# 03_MCU.net
KiCad netlist of a schematic drawn in Altium Designer
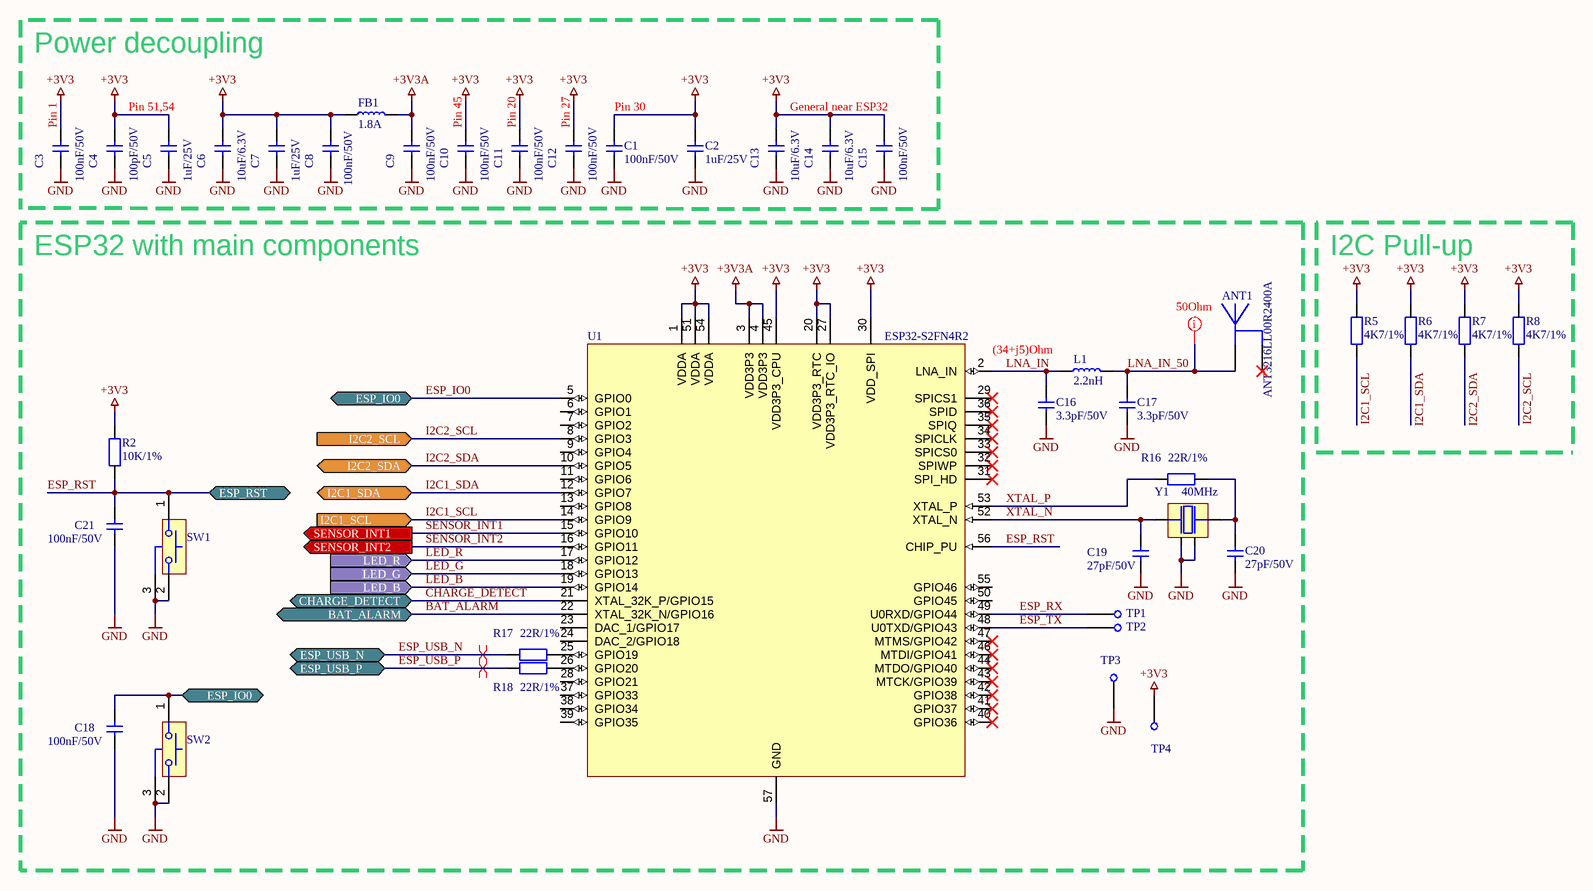
[diagram p0: 03 MCU.SchDoc]

(export (version "E")
  (design (tool "Eeschema 10.0.6"))
  (components
    (comp (ref "ANT1")
      (value "ANT3216LL00R2400A")
      (footprint "INDC3216X14N")
      (description "1206  Antennas ROHS")
      (fields (field (name "MANUFACTURER") "YAGEO"))
      (libsource (lib "altium_symbol") (part "ANT3216LL00R2400A"))
    )
    (comp (ref "C1")
      (value "100nF/50V")
      (footprint "CAPC1005X06N")
      (description "16V 100nF X7R ±10% 0402  Multilayer Ceramic Capacitors MLCC - SMD/SMT ROHS")
      (fields
        (field (name "MANUFACTURER") "Samsung Electro-Mechanics")
        (field (name "MFR_PART_NUMBER") "CL05B104KO5NNNC")
      )
      (libsource (lib "altium_symbol") (part "CL05B104KO5NNNC"))
    )
    (comp (ref "C2")
      (value "1uF/25V")
      (footprint "CAPC1005X06N")
      (description "25V 1uF X5R ±10% 0402  Multilayer Ceramic Capacitors MLCC - SMD/SMT ROHS")
      (fields
        (field (name "MANUFACTURER") "Samsung Electro-Mechanics")
        (field (name "MFR_PART_NUMBER") "CL05A105KA5NQNC")
      )
      (libsource (lib "altium_symbol") (part "CL05A105KA5NQNC"))
    )
    (comp (ref "C3")
      (value "100nF/50V")
      (footprint "CAPC1005X06N")
      (description "16V 100nF X7R ±10% 0402  Multilayer Ceramic Capacitors MLCC - SMD/SMT ROHS")
      (fields
        (field (name "MANUFACTURER") "Samsung Electro-Mechanics")
        (field (name "MFR_PART_NUMBER") "CL05B104KO5NNNC")
      )
      (libsource (lib "altium_symbol") (part "CL05B104KO5NNNC"))
    )
    (comp (ref "C4")
      (value "100pF/50V")
      (footprint "CAPC1005X06N")
      (description "50V 100pF C0G ±5% 0402  Multilayer Ceramic Capacitors MLCC - SMD/SMT ROHS")
      (fields
        (field (name "MANUFACTURER") "FH (Guangdong Fenghua Advanced Tech)")
        (field (name "MFR_PART_NUMBER") "0402CG101J500NT")
      )
      (libsource (lib "altium_symbol") (part "0402CG101J500NT"))
    )
    (comp (ref "C5")
      (value "1uF/25V")
      (footprint "CAPC1005X06N")
      (description "25V 1uF X5R ±10% 0402  Multilayer Ceramic Capacitors MLCC - SMD/SMT ROHS")
      (fields
        (field (name "MANUFACTURER") "Samsung Electro-Mechanics")
        (field (name "MFR_PART_NUMBER") "CL05A105KA5NQNC")
      )
      (libsource (lib "altium_symbol") (part "CL05A105KA5NQNC"))
    )
    (comp (ref "C6")
      (value "10uF/6.3V")
      (footprint "CAPC1005X06N")
      (description "6.3V 10uF X5R ±20% 0402  Multilayer Ceramic Capacitors MLCC - SMD/SMT ROHS")
      (fields
        (field (name "MANUFACTURER") "Samsung Electro-Mechanics")
        (field (name "MFR_PART_NUMBER") "CL05A106MQ5NUNC")
      )
      (libsource (lib "altium_symbol") (part "CL05A106MQ5NUNC"))
    )
    (comp (ref "C7")
      (value "1uF/25V")
      (footprint "CAPC1005X06N")
      (description "25V 1uF X5R ±10% 0402  Multilayer Ceramic Capacitors MLCC - SMD/SMT ROHS")
      (fields
        (field (name "MANUFACTURER") "Samsung Electro-Mechanics")
        (field (name "MFR_PART_NUMBER") "CL05A105KA5NQNC")
      )
      (libsource (lib "altium_symbol") (part "CL05A105KA5NQNC"))
    )
    (comp (ref "C8")
      (value "100nF/50V")
      (footprint "CAPC1005X06N")
      (description "16V 100nF X7R ±10% 0402  Multilayer Ceramic Capacitors MLCC - SMD/SMT ROHS")
      (fields
        (field (name "MANUFACTURER") "Samsung Electro-Mechanics")
        (field (name "MFR_PART_NUMBER") "CL05B104KO5NNNC")
      )
      (libsource (lib "altium_symbol") (part "CL05B104KO5NNNC"))
    )
    (comp (ref "C9")
      (value "100nF/50V")
      (footprint "CAPC1005X06N")
      (description "16V 100nF X7R ±10% 0402  Multilayer Ceramic Capacitors MLCC - SMD/SMT ROHS")
      (fields
        (field (name "MANUFACTURER") "Samsung Electro-Mechanics")
        (field (name "MFR_PART_NUMBER") "CL05B104KO5NNNC")
      )
      (libsource (lib "altium_symbol") (part "CL05B104KO5NNNC"))
    )
    (comp (ref "C10")
      (value "100nF/50V")
      (footprint "CAPC1005X06N")
      (description "16V 100nF X7R ±10% 0402  Multilayer Ceramic Capacitors MLCC - SMD/SMT ROHS")
      (fields
        (field (name "MANUFACTURER") "Samsung Electro-Mechanics")
        (field (name "MFR_PART_NUMBER") "CL05B104KO5NNNC")
      )
      (libsource (lib "altium_symbol") (part "CL05B104KO5NNNC"))
    )
    (comp (ref "C11")
      (value "100nF/50V")
      (footprint "CAPC1005X06N")
      (description "16V 100nF X7R ±10% 0402  Multilayer Ceramic Capacitors MLCC - SMD/SMT ROHS")
      (fields
        (field (name "MANUFACTURER") "Samsung Electro-Mechanics")
        (field (name "MFR_PART_NUMBER") "CL05B104KO5NNNC")
      )
      (libsource (lib "altium_symbol") (part "CL05B104KO5NNNC"))
    )
    (comp (ref "C12")
      (value "100nF/50V")
      (footprint "CAPC1005X06N")
      (description "16V 100nF X7R ±10% 0402  Multilayer Ceramic Capacitors MLCC - SMD/SMT ROHS")
      (fields
        (field (name "MANUFACTURER") "Samsung Electro-Mechanics")
        (field (name "MFR_PART_NUMBER") "CL05B104KO5NNNC")
      )
      (libsource (lib "altium_symbol") (part "CL05B104KO5NNNC"))
    )
    (comp (ref "C13")
      (value "10uF/6.3V")
      (footprint "CAPC1005X06N")
      (description "6.3V 10uF X5R ±20% 0402  Multilayer Ceramic Capacitors MLCC - SMD/SMT ROHS")
      (fields
        (field (name "MANUFACTURER") "Samsung Electro-Mechanics")
        (field (name "MFR_PART_NUMBER") "CL05A106MQ5NUNC")
      )
      (libsource (lib "altium_symbol") (part "CL05A106MQ5NUNC"))
    )
    (comp (ref "C14")
      (value "10uF/6.3V")
      (footprint "CAPC1005X06N")
      (description "6.3V 10uF X5R ±20% 0402  Multilayer Ceramic Capacitors MLCC - SMD/SMT ROHS")
      (fields
        (field (name "MANUFACTURER") "Samsung Electro-Mechanics")
        (field (name "MFR_PART_NUMBER") "CL05A106MQ5NUNC")
      )
      (libsource (lib "altium_symbol") (part "CL05A106MQ5NUNC"))
    )
    (comp (ref "C15")
      (value "100nF/50V")
      (footprint "CAPC1005X06N")
      (description "16V 100nF X7R ±10% 0402  Multilayer Ceramic Capacitors MLCC - SMD/SMT ROHS")
      (fields
        (field (name "MANUFACTURER") "Samsung Electro-Mechanics")
        (field (name "MFR_PART_NUMBER") "CL05B104KO5NNNC")
      )
      (libsource (lib "altium_symbol") (part "CL05B104KO5NNNC"))
    )
    (comp (ref "C16")
      (value "3.3pF/50V")
      (footprint "CAPC1005X06N")
      (description "50V 3.3pF C0G ±0.25pF 0402  Multilayer Ceramic Capacitors MLCC - SMD/SMT ROHS")
      (fields
        (field (name "MANUFACTURER") "FH (Guangdong Fenghua Advanced Tech)")
        (field (name "MFR_PART_NUMBER") "0402CG3R3C500NT")
      )
      (libsource (lib "altium_symbol") (part "0402CG3R3C500NT"))
    )
    (comp (ref "C17")
      (value "3.3pF/50V")
      (footprint "CAPC1005X06N")
      (description "50V 3.3pF C0G ±0.25pF 0402  Multilayer Ceramic Capacitors MLCC - SMD/SMT ROHS")
      (fields
        (field (name "MANUFACTURER") "FH (Guangdong Fenghua Advanced Tech)")
        (field (name "MFR_PART_NUMBER") "0402CG3R3C500NT")
      )
      (libsource (lib "altium_symbol") (part "0402CG3R3C500NT"))
    )
    (comp (ref "C18")
      (value "100nF/50V")
      (footprint "CAPC1005X06N")
      (description "16V 100nF X7R ±10% 0402  Multilayer Ceramic Capacitors MLCC - SMD/SMT ROHS")
      (fields
        (field (name "MANUFACTURER") "Samsung Electro-Mechanics")
        (field (name "MFR_PART_NUMBER") "CL05B104KO5NNNC")
      )
      (libsource (lib "altium_symbol") (part "CL05B104KO5NNNC"))
    )
    (comp (ref "C19")
      (value "27pF/50V")
      (footprint "CAPC1005X06N")
      (description "50V 27pF C0G ±5% 0402  Multilayer Ceramic Capacitors MLCC - SMD/SMT ROHS")
      (fields
        (field (name "MANUFACTURER") "FH (Guangdong Fenghua Advanced Tech)")
        (field (name "MFR_PART_NUMBER") "0402CG270J500NT")
      )
      (libsource (lib "altium_symbol") (part "0402CG270J500NT"))
    )
    (comp (ref "C20")
      (value "27pF/50V")
      (footprint "CAPC1005X06N")
      (description "50V 27pF C0G ±5% 0402  Multilayer Ceramic Capacitors MLCC - SMD/SMT ROHS")
      (fields
        (field (name "MANUFACTURER") "FH (Guangdong Fenghua Advanced Tech)")
        (field (name "MFR_PART_NUMBER") "0402CG270J500NT")
      )
      (libsource (lib "altium_symbol") (part "0402CG270J500NT"))
    )
    (comp (ref "C21")
      (value "100nF/50V")
      (footprint "CAPC1005X06N")
      (description "16V 100nF X7R ±10% 0402  Multilayer Ceramic Capacitors MLCC - SMD/SMT ROHS")
      (fields
        (field (name "MANUFACTURER") "Samsung Electro-Mechanics")
        (field (name "MFR_PART_NUMBER") "CL05B104KO5NNNC")
      )
      (libsource (lib "altium_symbol") (part "CL05B104KO5NNNC"))
    )
    (comp (ref "FB1")
      (value "1.8A")
      (footprint "INDC1608X10N")
      (description "1.8A 1 60mΩ 30Ω@100MHz ±25% 0603  Ferrite Beads ROHS")
      (fields (field (name "MANUFACTURER") "Sunlord") (field (name "MFR_PART_NUMBER") "UPZ1608G300-1R8TF"))
      (libsource (lib "altium_symbol") (part "UPZ1608G300-1R8TF"))
    )
    (comp (ref "L1")
      (value "2.2nH")
      (footprint "INDC1005X05N")
      (description "400mA 2.2nH ±0.3nH 120mΩ 0402  Inductors (SMD) ROHS")
      (fields
        (field (name "MANUFACTURER") "Chilisin Elec")
        (field (name "MFR_PART_NUMBER") "CLH1005T-2N2S-S")
      )
      (libsource (lib "altium_symbol") (part "CLH1005T-2N2S-S"))
    )
    (comp (ref "R2")
      (value "10K/1%")
      (footprint "RESC1005X04N")
      (fields
        (field (name "MANUFACTURER") "UNI-ROYAL(Uniroyal Elec)")
        (field (name "MFR_PART_NUMBER") "0402WGF1002TCE")
      )
      (libsource (lib "altium_symbol") (part "0402WGF1002TCE"))
    )
    (comp (ref "R5")
      (value "4K7/1%")
      (footprint "RESC1005X04N")
      (fields (field (name "MANUFACTURER") "Viking Tech") (field (name "MFR_PART_NUMBER") "CR-02FL6---4K7"))
      (libsource (lib "altium_symbol") (part "CR-02FL6---4K7"))
    )
    (comp (ref "R6")
      (value "4K7/1%")
      (footprint "RESC1005X04N")
      (fields (field (name "MANUFACTURER") "Viking Tech") (field (name "MFR_PART_NUMBER") "CR-02FL6---4K7"))
      (libsource (lib "altium_symbol") (part "CR-02FL6---4K7"))
    )
    (comp (ref "R7")
      (value "4K7/1%")
      (footprint "RESC1005X04N")
      (fields (field (name "MANUFACTURER") "Viking Tech") (field (name "MFR_PART_NUMBER") "CR-02FL6---4K7"))
      (libsource (lib "altium_symbol") (part "CR-02FL6---4K7"))
    )
    (comp (ref "R8")
      (value "4K7/1%")
      (footprint "RESC1005X04N")
      (fields (field (name "MANUFACTURER") "Viking Tech") (field (name "MFR_PART_NUMBER") "CR-02FL6---4K7"))
      (libsource (lib "altium_symbol") (part "CR-02FL6---4K7"))
    )
    (comp (ref "R16")
      (value "22R/1%")
      (footprint "RESC1005X04N")
      (fields
        (field (name "MANUFACTURER") "UNI-ROYAL(Uniroyal Elec)")
        (field (name "MFR_PART_NUMBER") "0402WGF220JTCE")
      )
      (libsource (lib "altium_symbol") (part "0402WGF220JTCE"))
    )
    (comp (ref "R17")
      (value "22R/1%")
      (footprint "RESC1005X04N")
      (fields
        (field (name "MANUFACTURER") "UNI-ROYAL(Uniroyal Elec)")
        (field (name "MFR_PART_NUMBER") "0402WGF220JTCE")
      )
      (libsource (lib "altium_symbol") (part "0402WGF220JTCE"))
    )
    (comp (ref "R18")
      (value "22R/1%")
      (footprint "RESC1005X04N")
      (fields
        (field (name "MANUFACTURER") "UNI-ROYAL(Uniroyal Elec)")
        (field (name "MFR_PART_NUMBER") "0402WGF220JTCE")
      )
      (libsource (lib "altium_symbol") (part "0402WGF220JTCE"))
    )
    (comp (ref "SW1")
      (value "PUSH BUTTON SMD")
      (footprint "1TS003B-1400-3500A-CT")
      (fields
        (field (name "MANUFACTURER") "HYP (Hongyuan Precision)")
        (field (name "MFR_PART_NUMBER") "1TS003B-1400-3500A-CT")
      )
      (libsource (lib "altium_symbol") (part "1TS003B-1400-3500A-CT"))
    )
    (comp (ref "SW2")
      (value "PUSH BUTTON SMD")
      (footprint "1TS003B-1400-3500A-CT")
      (fields
        (field (name "MANUFACTURER") "HYP (Hongyuan Precision)")
        (field (name "MFR_PART_NUMBER") "1TS003B-1400-3500A-CT")
      )
      (libsource (lib "altium_symbol") (part "1TS003B-1400-3500A-CT"))
    )
    (comp (ref "TP1")
      (value "Test Point 1mm")
      (footprint "TEST_POINT_1mm")
      (libsource (lib "altium_symbol") (part "TestPoint"))
    )
    (comp (ref "TP2")
      (value "Test Point 1mm")
      (footprint "TEST_POINT_1mm")
      (libsource (lib "altium_symbol") (part "TestPoint"))
    )
    (comp (ref "TP3")
      (value "Test Point 1mm")
      (footprint "TEST_POINT_1mm")
      (libsource (lib "altium_symbol") (part "TestPoint"))
    )
    (comp (ref "TP4")
      (value "Test Point 1mm")
      (footprint "TEST_POINT_1mm")
      (libsource (lib "altium_symbol") (part "TestPoint"))
    )
    (comp (ref "U1")
      (value "ESP32-S2FN4R2")
      (footprint "QFN40P700X700X90_HS-57N")
      (description "QFN-56  RF Modules ROHS")
      (fields (field (name "MANUFACTURER") "Espressif Systems"))
      (libsource (lib "altium_symbol") (part "ESP32-S2FN4R2"))
    )
    (comp (ref "Y1")
      (value "40MHz")
      (footprint "7E40000E15UCG")
      (description "40MHz SMD Crystal Resonator 15pF ±10ppm ±30ppm -40℃~+85℃ SMD2520-4P  Crystals ROHS")
      (fields
        (field (name "MANUFACTURER") "SJK(SHENZHEN CRYSTAL TECH)")
        (field (name "MFR_PART_NUMBER") "7E40000E15UCG")
      )
      (libsource (lib "altium_symbol") (part "7E40000E15UCG"))
    )
  )
  (nets
    (net (code "1") (name "+3V3") (class "Default")
      (node (ref "C1") (pin "2") (pinfunction "2_2") (pintype "passive"))
      (node (ref "C10") (pin "2") (pinfunction "2_2") (pintype "passive"))
      (node (ref "C11") (pin "2") (pinfunction "2_2") (pintype "passive"))
      (node (ref "C12") (pin "2") (pinfunction "2_2") (pintype "passive"))
      (node (ref "C13") (pin "1") (pinfunction "1_1") (pintype "passive"))
      (node (ref "C14") (pin "1") (pinfunction "1_1") (pintype "passive"))
      (node (ref "C15") (pin "2") (pinfunction "2_2") (pintype "passive"))
      (node (ref "C2") (pin "2") (pinfunction "2_2") (pintype "passive"))
      (node (ref "C3") (pin "2") (pinfunction "2_2") (pintype "passive"))
      (node (ref "C4") (pin "2") (pinfunction "2_2") (pintype "passive"))
      (node (ref "C5") (pin "2") (pinfunction "2_2") (pintype "passive"))
      (node (ref "C6") (pin "2") (pinfunction "2_2") (pintype "passive"))
      (node (ref "C7") (pin "2") (pinfunction "2_2") (pintype "passive"))
      (node (ref "C8") (pin "2") (pinfunction "2_2") (pintype "passive"))
      (node (ref "FB1") (pin "1") (pinfunction "1_1") (pintype "passive"))
      (node (ref "R2") (pin "1") (pinfunction "1_1") (pintype "passive"))
      (node (ref "R5") (pin "2") (pinfunction "2_2") (pintype "passive"))
      (node (ref "R6") (pin "2") (pinfunction "2_2") (pintype "passive"))
      (node (ref "R7") (pin "2") (pinfunction "2_2") (pintype "passive"))
      (node (ref "R8") (pin "2") (pinfunction "2_2") (pintype "passive"))
      (node (ref "TP4") (pin "1") (pinfunction "1_1") (pintype "passive"))
      (node (ref "U1") (pin "1") (pinfunction "VDDA_1") (pintype "power_in"))
      (node (ref "U1") (pin "20") (pinfunction "VDD3P3_RTC_20") (pintype "power_in"))
      (node (ref "U1") (pin "27") (pinfunction "VDD3P3_RTC_IO_27") (pintype "power_in"))
      (node (ref "U1") (pin "30") (pinfunction "VDD_SPI_30") (pintype "power_in"))
      (node (ref "U1") (pin "45") (pinfunction "VDD3P3_CPU_45") (pintype "power_in"))
      (node (ref "U1") (pin "51") (pinfunction "VDDA_51") (pintype "passive"))
      (node (ref "U1") (pin "54") (pinfunction "VDDA_54") (pintype "passive"))
    )
    (net (code "2") (name "+3V3A") (class "Default")
      (node (ref "C9") (pin "2") (pinfunction "2_2") (pintype "passive"))
      (node (ref "FB1") (pin "2") (pinfunction "2_2") (pintype "passive"))
      (node (ref "U1") (pin "3") (pinfunction "VDD3P3_3") (pintype "power_in"))
      (node (ref "U1") (pin "4") (pinfunction "VDD3P3_4") (pintype "power_in"))
    )
    (net (code "3") (name "/BAT_ALARM") (class "Default")
      (node (ref "U1") (pin "22") (pinfunction "XTAL_32K_N/GPIO16_22") (pintype "passive"))
    )
    (net (code "4") (name "/CHARGE_DETECT") (class "Default")
      (node (ref "U1") (pin "21") (pinfunction "XTAL_32K_P/GPIO15_21") (pintype "passive"))
    )
    (net (code "5") (name "/ESP_IO0") (class "Default")
      (node (ref "C18") (pin "2") (pinfunction "2_2") (pintype "passive"))
      (node (ref "SW2") (pin "1") (pinfunction "1_1") (pintype "passive"))
      (node (ref "U1") (pin "5") (pinfunction "GPIO0_5") (pintype "bidirectional"))
    )
    (net (code "6") (name "/ESP_RST") (class "Default")
      (node (ref "C21") (pin "2") (pinfunction "2_2") (pintype "passive"))
      (node (ref "R2") (pin "2") (pinfunction "2_2") (pintype "passive"))
      (node (ref "SW1") (pin "1") (pinfunction "1_1") (pintype "passive"))
      (node (ref "U1") (pin "56") (pinfunction "CHIP_PU_56") (pintype "input"))
    )
    (net (code "7") (name "/ESP_RX") (class "Default")
      (node (ref "TP1") (pin "1") (pinfunction "1_1") (pintype "passive"))
      (node (ref "U1") (pin "49") (pinfunction "U0RXD/GPIO44_49") (pintype "bidirectional"))
    )
    (net (code "8") (name "/ESP_TX") (class "Default")
      (node (ref "TP2") (pin "1") (pinfunction "1_1") (pintype "passive"))
      (node (ref "U1") (pin "48") (pinfunction "U0TXD/GPIO43_48") (pintype "bidirectional"))
    )
    (net (code "9") (name "/ESP_USB_N") (class "Default")
      (node (ref "R17") (pin "1") (pinfunction "1_1") (pintype "passive"))
    )
    (net (code "10") (name "/ESP_USB_P") (class "Default")
      (node (ref "R18") (pin "1") (pinfunction "1_1") (pintype "passive"))
    )
    (net (code "11") (name "/I2C1_SCL") (class "Default")
      (node (ref "R5") (pin "1") (pinfunction "1_1") (pintype "passive"))
      (node (ref "U1") (pin "14") (pinfunction "GPIO9_14") (pintype "bidirectional"))
    )
    (net (code "12") (name "/I2C1_SDA") (class "Default")
      (node (ref "R6") (pin "1") (pinfunction "1_1") (pintype "passive"))
      (node (ref "U1") (pin "12") (pinfunction "GPIO7_12") (pintype "bidirectional"))
    )
    (net (code "13") (name "/I2C2_SCL") (class "Default")
      (node (ref "R8") (pin "1") (pinfunction "1_1") (pintype "passive"))
      (node (ref "U1") (pin "8") (pinfunction "GPIO3_8") (pintype "bidirectional"))
    )
    (net (code "14") (name "/I2C2_SDA") (class "Default")
      (node (ref "R7") (pin "1") (pinfunction "1_1") (pintype "passive"))
      (node (ref "U1") (pin "10") (pinfunction "GPIO5_10") (pintype "bidirectional"))
    )
    (net (code "15") (name "/LED_B") (class "Default")
      (node (ref "U1") (pin "19") (pinfunction "GPIO14_19") (pintype "bidirectional"))
    )
    (net (code "16") (name "/LED_G") (class "Default")
      (node (ref "U1") (pin "18") (pinfunction "GPIO13_18") (pintype "bidirectional"))
    )
    (net (code "17") (name "/LED_R") (class "Default")
      (node (ref "U1") (pin "17") (pinfunction "GPIO12_17") (pintype "bidirectional"))
    )
    (net (code "18") (name "/LNA_IN") (class "Default")
      (node (ref "C16") (pin "2") (pinfunction "2_2") (pintype "passive"))
      (node (ref "L1") (pin "1") (pinfunction "1_1") (pintype "passive"))
      (node (ref "U1") (pin "2") (pinfunction "LNA_IN_2") (pintype "bidirectional"))
    )
    (net (code "19") (name "/LNA_IN_50") (class "Default")
      (node (ref "ANT1") (pin "1") (pinfunction "1_1") (pintype "passive"))
      (node (ref "C17") (pin "2") (pinfunction "2_2") (pintype "passive"))
      (node (ref "L1") (pin "2") (pinfunction "2_2") (pintype "passive"))
    )
    (net (code "20") (name "/SENSOR_INT1") (class "Default")
      (node (ref "U1") (pin "15") (pinfunction "GPIO10_15") (pintype "bidirectional"))
    )
    (net (code "21") (name "/SENSOR_INT2") (class "Default")
      (node (ref "U1") (pin "16") (pinfunction "GPIO11_16") (pintype "bidirectional"))
    )
    (net (code "22") (name "/XTAL_N") (class "Default")
      (node (ref "C19") (pin "2") (pinfunction "2_2") (pintype "passive"))
      (node (ref "U1") (pin "52") (pinfunction "XTAL_N_52") (pintype "input"))
      (node (ref "Y1") (pin "1") (pinfunction "1_1") (pintype "passive"))
    )
    (net (code "23") (name "/XTAL_P") (class "Default")
      (node (ref "R16") (pin "1") (pinfunction "1_1") (pintype "passive"))
      (node (ref "U1") (pin "53") (pinfunction "XTAL_P_53") (pintype "input"))
    )
    (net (code "24") (name "GND") (class "Default")
      (node (ref "C1") (pin "1") (pinfunction "1_1") (pintype "passive"))
      (node (ref "C10") (pin "1") (pinfunction "1_1") (pintype "passive"))
      (node (ref "C11") (pin "1") (pinfunction "1_1") (pintype "passive"))
      (node (ref "C12") (pin "1") (pinfunction "1_1") (pintype "passive"))
      (node (ref "C13") (pin "2") (pinfunction "2_2") (pintype "passive"))
      (node (ref "C14") (pin "2") (pinfunction "2_2") (pintype "passive"))
      (node (ref "C15") (pin "1") (pinfunction "1_1") (pintype "passive"))
      (node (ref "C16") (pin "1") (pinfunction "1_1") (pintype "passive"))
      (node (ref "C17") (pin "1") (pinfunction "1_1") (pintype "passive"))
      (node (ref "C18") (pin "1") (pinfunction "1_1") (pintype "passive"))
      (node (ref "C19") (pin "1") (pinfunction "1_1") (pintype "passive"))
      (node (ref "C2") (pin "1") (pinfunction "1_1") (pintype "passive"))
      (node (ref "C20") (pin "1") (pinfunction "1_1") (pintype "passive"))
      (node (ref "C21") (pin "1") (pinfunction "1_1") (pintype "passive"))
      (node (ref "C3") (pin "1") (pinfunction "1_1") (pintype "passive"))
      (node (ref "C4") (pin "1") (pinfunction "1_1") (pintype "passive"))
      (node (ref "C5") (pin "1") (pinfunction "1_1") (pintype "passive"))
      (node (ref "C6") (pin "1") (pinfunction "1_1") (pintype "passive"))
      (node (ref "C7") (pin "1") (pinfunction "1_1") (pintype "passive"))
      (node (ref "C8") (pin "1") (pinfunction "1_1") (pintype "passive"))
      (node (ref "C9") (pin "1") (pinfunction "1_1") (pintype "passive"))
      (node (ref "SW1") (pin "2") (pinfunction "2_2") (pintype "passive"))
      (node (ref "SW1") (pin "3") (pinfunction "3_3") (pintype "passive"))
      (node (ref "SW2") (pin "2") (pinfunction "2_2") (pintype "passive"))
      (node (ref "SW2") (pin "3") (pinfunction "3_3") (pintype "passive"))
      (node (ref "TP3") (pin "1") (pinfunction "1_1") (pintype "passive"))
      (node (ref "U1") (pin "57") (pinfunction "GND_57") (pintype "passive"))
      (node (ref "Y1") (pin "2") (pinfunction "2_2") (pintype "passive"))
      (node (ref "Y1") (pin "4") (pinfunction "4_4") (pintype "passive"))
    )
    (net (code "25") (name "Net-(C20-Pad2)") (class "Default")
      (node (ref "C20") (pin "2") (pinfunction "2_2") (pintype "passive"))
      (node (ref "R16") (pin "2") (pinfunction "2_2") (pintype "passive"))
      (node (ref "Y1") (pin "3") (pinfunction "3_3") (pintype "passive"))
    )
    (net (code "26") (name "Net-(U1-GPIO19)") (class "Default")
      (node (ref "R17") (pin "2") (pinfunction "2_2") (pintype "passive"))
      (node (ref "U1") (pin "25") (pinfunction "GPIO19_25") (pintype "bidirectional"))
    )
    (net (code "27") (name "Net-(U1-GPIO20)") (class "Default")
      (node (ref "R18") (pin "2") (pinfunction "2_2") (pintype "passive"))
      (node (ref "U1") (pin "26") (pinfunction "GPIO20_26") (pintype "bidirectional"))
    )
    (net (code "28") (name "unconnected-(ANT1-Pad2)") (class "Default")
      (node (ref "ANT1") (pin "2") (pinfunction "2_2") (pintype "passive+no_connect"))
    )
    (net (code "29") (name "unconnected-(U1-DAC_1{slash}GPIO17-Pad23)") (class "Default")
      (node (ref "U1") (pin "23") (pinfunction "DAC_1/GPIO17_23") (pintype "passive"))
    )
    (net (code "30") (name "unconnected-(U1-DAC_2{slash}GPIO18-Pad24)") (class "Default")
      (node (ref "U1") (pin "24") (pinfunction "DAC_2/GPIO18_24") (pintype "passive"))
    )
    (net (code "31") (name "unconnected-(U1-GPIO1-Pad6)") (class "Default")
      (node (ref "U1") (pin "6") (pinfunction "GPIO1_6") (pintype "bidirectional"))
    )
    (net (code "32") (name "unconnected-(U1-GPIO2-Pad7)") (class "Default")
      (node (ref "U1") (pin "7") (pinfunction "GPIO2_7") (pintype "bidirectional"))
    )
    (net (code "33") (name "unconnected-(U1-GPIO4-Pad9)") (class "Default")
      (node (ref "U1") (pin "9") (pinfunction "GPIO4_9") (pintype "bidirectional"))
    )
    (net (code "34") (name "unconnected-(U1-GPIO6-Pad11)") (class "Default")
      (node (ref "U1") (pin "11") (pinfunction "GPIO6_11") (pintype "bidirectional"))
    )
    (net (code "35") (name "unconnected-(U1-GPIO8-Pad13)") (class "Default")
      (node (ref "U1") (pin "13") (pinfunction "GPIO8_13") (pintype "bidirectional"))
    )
    (net (code "36") (name "unconnected-(U1-GPIO21-Pad28)") (class "Default")
      (node (ref "U1") (pin "28") (pinfunction "GPIO21_28") (pintype "bidirectional"))
    )
    (net (code "37") (name "unconnected-(U1-GPIO33-Pad37)") (class "Default")
      (node (ref "U1") (pin "37") (pinfunction "GPIO33_37") (pintype "bidirectional"))
    )
    (net (code "38") (name "unconnected-(U1-GPIO34-Pad38)") (class "Default")
      (node (ref "U1") (pin "38") (pinfunction "GPIO34_38") (pintype "bidirectional"))
    )
    (net (code "39") (name "unconnected-(U1-GPIO35-Pad39)") (class "Default")
      (node (ref "U1") (pin "39") (pinfunction "GPIO35_39") (pintype "bidirectional"))
    )
    (net (code "40") (name "unconnected-(U1-GPIO36-Pad40)") (class "Default")
      (node (ref "U1") (pin "40") (pinfunction "GPIO36_40") (pintype "bidirectional+no_connect"))
    )
    (net (code "41") (name "unconnected-(U1-GPIO37-Pad41)") (class "Default")
      (node (ref "U1") (pin "41") (pinfunction "GPIO37_41") (pintype "bidirectional+no_connect"))
    )
    (net (code "42") (name "unconnected-(U1-GPIO38-Pad42)") (class "Default")
      (node (ref "U1") (pin "42") (pinfunction "GPIO38_42") (pintype "bidirectional+no_connect"))
    )
    (net (code "43") (name "unconnected-(U1-GPIO45-Pad50)") (class "Default")
      (node (ref "U1") (pin "50") (pinfunction "GPIO45_50") (pintype "bidirectional"))
    )
    (net (code "44") (name "unconnected-(U1-GPIO46-Pad55)") (class "Default")
      (node (ref "U1") (pin "55") (pinfunction "GPIO46_55") (pintype "bidirectional"))
    )
    (net (code "45") (name "unconnected-(U1-MTCK{slash}GPIO39-Pad43)") (class "Default")
      (node (ref "U1") (pin "43") (pinfunction "MTCK/GPIO39_43") (pintype "bidirectional+no_connect"))
    )
    (net (code "46") (name "unconnected-(U1-MTDI{slash}GPIO41-Pad46)") (class "Default")
      (node (ref "U1") (pin "46") (pinfunction "MTDI/GPIO41_46") (pintype "bidirectional+no_connect"))
    )
    (net (code "47") (name "unconnected-(U1-MTDO{slash}GPIO40-Pad44)") (class "Default")
      (node (ref "U1") (pin "44") (pinfunction "MTDO/GPIO40_44") (pintype "bidirectional+no_connect"))
    )
    (net (code "48") (name "unconnected-(U1-MTMS{slash}GPIO42-Pad47)") (class "Default")
      (node (ref "U1") (pin "47") (pinfunction "MTMS/GPIO42_47") (pintype "bidirectional+no_connect"))
    )
    (net (code "49") (name "unconnected-(U1-SPICLK-Pad34)") (class "Default")
      (node (ref "U1") (pin "34") (pinfunction "SPICLK_34") (pintype "passive+no_connect"))
    )
    (net (code "50") (name "unconnected-(U1-SPICS0-Pad33)") (class "Default")
      (node (ref "U1") (pin "33") (pinfunction "SPICS0_33") (pintype "passive+no_connect"))
    )
    (net (code "51") (name "unconnected-(U1-SPICS1-Pad29)") (class "Default")
      (node (ref "U1") (pin "29") (pinfunction "SPICS1_29") (pintype "passive+no_connect"))
    )
    (net (code "52") (name "unconnected-(U1-SPID-Pad36)") (class "Default")
      (node (ref "U1") (pin "36") (pinfunction "SPID_36") (pintype "passive+no_connect"))
    )
    (net (code "53") (name "unconnected-(U1-SPIQ-Pad35)") (class "Default")
      (node (ref "U1") (pin "35") (pinfunction "SPIQ_35") (pintype "passive+no_connect"))
    )
    (net (code "54") (name "unconnected-(U1-SPIWP-Pad32)") (class "Default")
      (node (ref "U1") (pin "32") (pinfunction "SPIWP_32") (pintype "passive+no_connect"))
    )
    (net (code "55") (name "unconnected-(U1-SPI_HD-Pad31)") (class "Default")
      (node (ref "U1") (pin "31") (pinfunction "SPI_HD_31") (pintype "passive+no_connect"))
    )
  )
)
